# Picc.net
KiCad netlist of a schematic drawn in Altium Designer
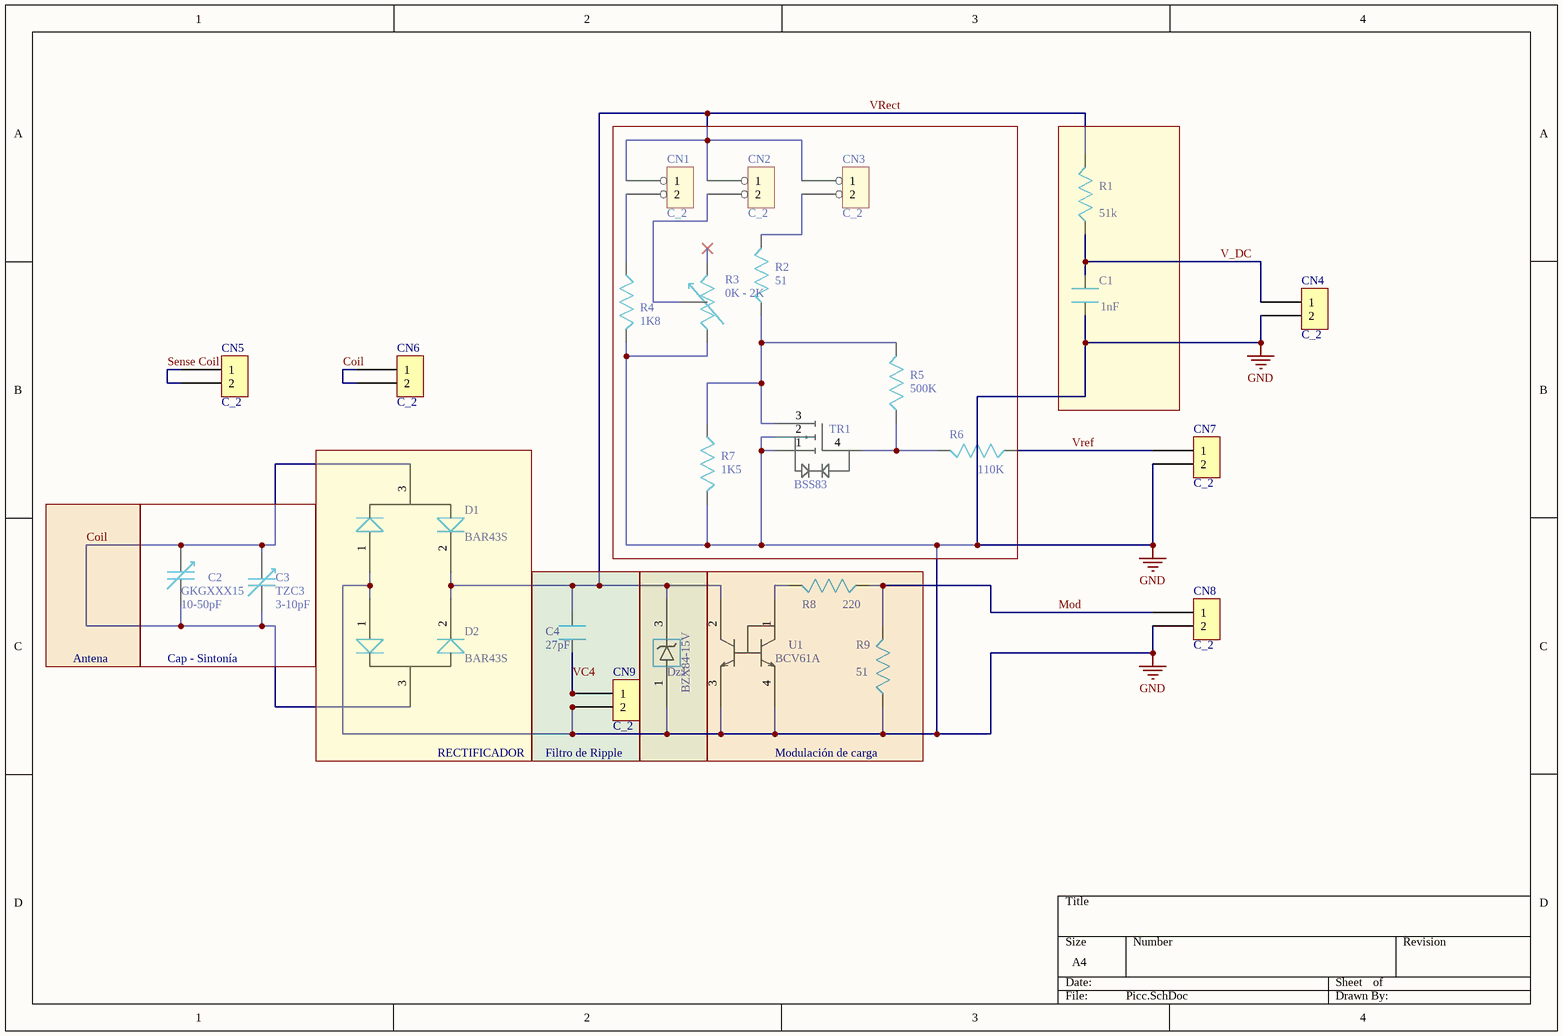
[diagram p0: Picc.SchDoc]

(export (version "E")
  (design (tool "Eeschema 10.0.6"))
  (components
    (comp (ref "C1")
      (value "1nF")
      (footprint "C_1210")
      (description "Ceramic Capacitor")
      (libsource (lib "BasicosyConectores") (part "Cap"))
    )
    (comp (ref "C2")
      (value "GKGXXX15")
      (footprint "GKGXXX15")
      (description "10")
      (fields (field (name "ALTIUM_UNNAMED_1") "10-50pF"))
      (libsource (lib "BasicosyConectores") (part "GKGXXX15"))
    )
    (comp (ref "C3")
      (value "TZC3")
      (footprint "TZC3")
      (fields (field (name "ALTIUM_UNNAMED_1") "3-10pF"))
      (libsource (lib "BasicosyConectores") (part "TZC3"))
    )
    (comp (ref "C4")
      (value "27pF")
      (footprint "C_1210")
      (description "Ceramic Capacitor")
      (libsource (lib "BasicosyConectores") (part "Cap"))
    )
    (comp (ref "CN1")
      (value "C_2")
      (footprint "2x1 Pin Array")
      (description "Conector 2 pines")
      (libsource (lib "BasicosyConectores") (part "C_2"))
    )
    (comp (ref "CN2")
      (value "C_2")
      (footprint "2x1 Pin Array")
      (description "Conector 2 pines")
      (libsource (lib "BasicosyConectores") (part "C_2"))
    )
    (comp (ref "CN3")
      (value "C_2")
      (footprint "2x1 Pin Array")
      (description "Conector 2 pines")
      (libsource (lib "BasicosyConectores") (part "C_2"))
    )
    (comp (ref "CN4")
      (value "C_2")
      (footprint "2x1 Pin Array")
      (description "Conector 2 pines")
      (libsource (lib "BasicosyConectores") (part "C_2"))
    )
    (comp (ref "CN5")
      (value "C_2")
      (footprint "2x1 Pin Array")
      (description "Conector 2 pines")
      (libsource (lib "BasicosyConectores") (part "C_2"))
    )
    (comp (ref "CN6")
      (value "C_2")
      (footprint "2x1 Pin Array")
      (description "Conector 2 pines")
      (libsource (lib "BasicosyConectores") (part "C_2"))
    )
    (comp (ref "CN7")
      (value "C_2")
      (footprint "2x1 Pin Array")
      (description "Conector 2 pines")
      (libsource (lib "BasicosyConectores") (part "C_2"))
    )
    (comp (ref "CN8")
      (value "C_2")
      (footprint "2x1 Pin Array")
      (description "Conector 2 pines")
      (libsource (lib "BasicosyConectores") (part "C_2"))
    )
    (comp (ref "CN9")
      (value "C_2")
      (footprint "2x1 Pin Array")
      (description "Conector 2 pines")
      (libsource (lib "BasicosyConectores") (part "C_2"))
    )
    (comp (ref "D1")
      (value "BAR43S")
      (footprint "BAR43S")
      (libsource (lib "BasicosyConectores") (part "BAR43S"))
    )
    (comp (ref "D2")
      (value "BAR43S")
      (footprint "BAR43S")
      (libsource (lib "BasicosyConectores") (part "BAR43S"))
    )
    (comp (ref "Dz1")
      (value "BZX84-15V")
      (footprint "BZX84")
      (libsource (lib "BasicosyConectores") (part "BZX84"))
    )
    (comp (ref "R1")
      (value "51k")
      (footprint "R_1210")
      (description "Chip Resistor")
      (libsource (lib "BasicosyConectores") (part "R"))
    )
    (comp (ref "R2")
      (value "51")
      (footprint "R_1210")
      (description "Chip Resistor")
      (libsource (lib "BasicosyConectores") (part "R"))
    )
    (comp (ref "R3")
      (value "0K - 2K")
      (footprint "Bourns 3224W")
      (description "SMD Potentiometer")
      (libsource (lib "BasicosyConectores") (part "Rvar"))
    )
    (comp (ref "R4")
      (value "1K8")
      (footprint "R_1210")
      (description "Chip Resistor")
      (libsource (lib "BasicosyConectores") (part "R"))
    )
    (comp (ref "R5")
      (value "500K")
      (footprint "R_1210")
      (description "Chip Resistor")
      (libsource (lib "BasicosyConectores") (part "R"))
    )
    (comp (ref "R6")
      (value "110K")
      (footprint "R_1210")
      (description "Chip Resistor")
      (libsource (lib "BasicosyConectores") (part "R"))
    )
    (comp (ref "R7")
      (value "1K5")
      (footprint "R_1210")
      (description "Chip Resistor")
      (libsource (lib "BasicosyConectores") (part "R"))
    )
    (comp (ref "R8")
      (value "220")
      (footprint "R_1210")
      (description "Chip Resistor")
      (libsource (lib "BasicosyConectores") (part "R"))
    )
    (comp (ref "R9")
      (value "51")
      (footprint "R_1210")
      (description "Chip Resistor")
      (libsource (lib "BasicosyConectores") (part "R"))
    )
    (comp (ref "TR1")
      (value "BSS83")
      (footprint "BSS83")
      (libsource (lib "BasicosyConectores") (part "BSS83"))
    )
    (comp (ref "U1")
      (value "BCV61A")
      (footprint "BCV61A")
      (libsource (lib "BasicosyConectores") (part "BCV61A"))
    )
  )
  (nets
    (net (code "1") (name "/Coil") (class "Default")
      (node (ref "C2") (pin "0") (pinfunction "0_0") (pintype "passive"))
      (node (ref "C2") (pin "1") (pinfunction "1_1") (pintype "passive"))
      (node (ref "C3") (pin "0") (pinfunction "0_0") (pintype "passive"))
      (node (ref "C3") (pin "1") (pinfunction "1_1") (pintype "passive"))
      (node (ref "CN6") (pin "1") (pinfunction "1_1") (pintype "passive"))
      (node (ref "CN6") (pin "2") (pinfunction "2_2") (pintype "passive"))
      (node (ref "D1") (pin "3") (pinfunction "3_3") (pintype "passive"))
      (node (ref "D2") (pin "3") (pinfunction "3_3") (pintype "passive"))
    )
    (net (code "2") (name "/Mod") (class "Default")
      (node (ref "CN8") (pin "1") (pinfunction "1_1") (pintype "passive"))
      (node (ref "R8") (pin "1") (pinfunction "1_1") (pintype "passive"))
      (node (ref "R9") (pin "2") (pinfunction "2_2") (pintype "passive"))
    )
    (net (code "3") (name "/Sense Coil") (class "Default")
      (node (ref "CN5") (pin "1") (pinfunction "1_1") (pintype "passive"))
      (node (ref "CN5") (pin "2") (pinfunction "2_2") (pintype "passive"))
    )
    (net (code "4") (name "/VC4") (class "Default")
      (node (ref "C4") (pin "1") (pinfunction "1_1") (pintype "passive"))
      (node (ref "CN9") (pin "1") (pinfunction "1_1") (pintype "passive"))
    )
    (net (code "5") (name "/VRect") (class "Default")
      (node (ref "C4") (pin "2") (pinfunction "2_2") (pintype "passive"))
      (node (ref "CN1") (pin "1") (pinfunction "1_1") (pintype "passive"))
      (node (ref "CN2") (pin "1") (pinfunction "1_1") (pintype "passive"))
      (node (ref "CN3") (pin "1") (pinfunction "1_1") (pintype "passive"))
      (node (ref "D1") (pin "2") (pinfunction "2_2") (pintype "passive"))
      (node (ref "D2") (pin "2") (pinfunction "2_2") (pintype "passive"))
      (node (ref "Dz1") (pin "3") (pinfunction "3_3") (pintype "passive"))
      (node (ref "R1") (pin "2") (pinfunction "2_2") (pintype "passive"))
      (node (ref "U1") (pin "2") (pinfunction "2_2") (pintype "passive"))
    )
    (net (code "6") (name "/V_DC") (class "Default")
      (node (ref "C1") (pin "2") (pinfunction "2_2") (pintype "passive"))
      (node (ref "CN4") (pin "1") (pinfunction "1_1") (pintype "passive"))
      (node (ref "R1") (pin "1") (pinfunction "1_1") (pintype "passive"))
    )
    (net (code "7") (name "/Vref") (class "Default")
      (node (ref "CN7") (pin "1") (pinfunction "1_1") (pintype "passive"))
      (node (ref "R6") (pin "1") (pinfunction "1_1") (pintype "passive"))
    )
    (net (code "8") (name "GND") (class "Default")
      (node (ref "C1") (pin "1") (pinfunction "1_1") (pintype "passive"))
      (node (ref "CN4") (pin "2") (pinfunction "2_2") (pintype "passive"))
      (node (ref "CN7") (pin "2") (pinfunction "2_2") (pintype "passive"))
      (node (ref "CN8") (pin "2") (pinfunction "2_2") (pintype "passive"))
      (node (ref "CN9") (pin "2") (pinfunction "2_2") (pintype "passive"))
      (node (ref "D1") (pin "1") (pinfunction "1_1") (pintype "passive"))
      (node (ref "D2") (pin "1") (pinfunction "1_1") (pintype "passive"))
      (node (ref "Dz1") (pin "1") (pinfunction "1_1") (pintype "passive"))
      (node (ref "R3") (pin "1") (pinfunction "1_1") (pintype "passive"))
      (node (ref "R4") (pin "2") (pinfunction "2_2") (pintype "passive"))
      (node (ref "R7") (pin "2") (pinfunction "2_2") (pintype "passive"))
      (node (ref "R9") (pin "1") (pinfunction "1_1") (pintype "passive"))
      (node (ref "TR1") (pin "1") (pinfunction "s_1") (pintype "passive"))
      (node (ref "TR1") (pin "2") (pinfunction "b_2") (pintype "passive"))
      (node (ref "U1") (pin "3") (pinfunction "3_3") (pintype "passive"))
      (node (ref "U1") (pin "4") (pinfunction "4_4") (pintype "passive"))
    )
    (net (code "9") (name "Net-(CN1-Pad2)") (class "Default")
      (node (ref "CN1") (pin "2") (pinfunction "2_2") (pintype "passive"))
      (node (ref "R4") (pin "1") (pinfunction "1_1") (pintype "passive"))
    )
    (net (code "10") (name "Net-(CN2-Pad2)") (class "Default")
      (node (ref "CN2") (pin "2") (pinfunction "2_2") (pintype "passive"))
      (node (ref "R3") (pin "3") (pinfunction "3_3") (pintype "passive"))
    )
    (net (code "11") (name "Net-(CN3-Pad2)") (class "Default")
      (node (ref "CN3") (pin "2") (pinfunction "2_2") (pintype "passive"))
      (node (ref "R2") (pin "2") (pinfunction "2_2") (pintype "passive"))
    )
    (net (code "12") (name "Net-(R8-Pad2)") (class "Default")
      (node (ref "R8") (pin "2") (pinfunction "2_2") (pintype "passive"))
      (node (ref "U1") (pin "1") (pinfunction "1_1") (pintype "passive"))
    )
    (net (code "13") (name "Net-(TR1-d)") (class "Default")
      (node (ref "R2") (pin "1") (pinfunction "1_1") (pintype "passive"))
      (node (ref "R5") (pin "2") (pinfunction "2_2") (pintype "passive"))
      (node (ref "R7") (pin "1") (pinfunction "1_1") (pintype "passive"))
      (node (ref "TR1") (pin "3") (pinfunction "d_3") (pintype "passive"))
    )
    (net (code "14") (name "Net-(TR1-g)") (class "Default")
      (node (ref "R5") (pin "1") (pinfunction "1_1") (pintype "passive"))
      (node (ref "R6") (pin "2") (pinfunction "2_2") (pintype "passive"))
      (node (ref "TR1") (pin "4") (pinfunction "g_4") (pintype "passive"))
    )
    (net (code "15") (name "unconnected-(R3-Pad2)") (class "Default")
      (node (ref "R3") (pin "2") (pinfunction "2_2") (pintype "passive+no_connect"))
    )
  )
)
